# NanoModem.net
KiCad netlist of a schematic drawn in EAGLE
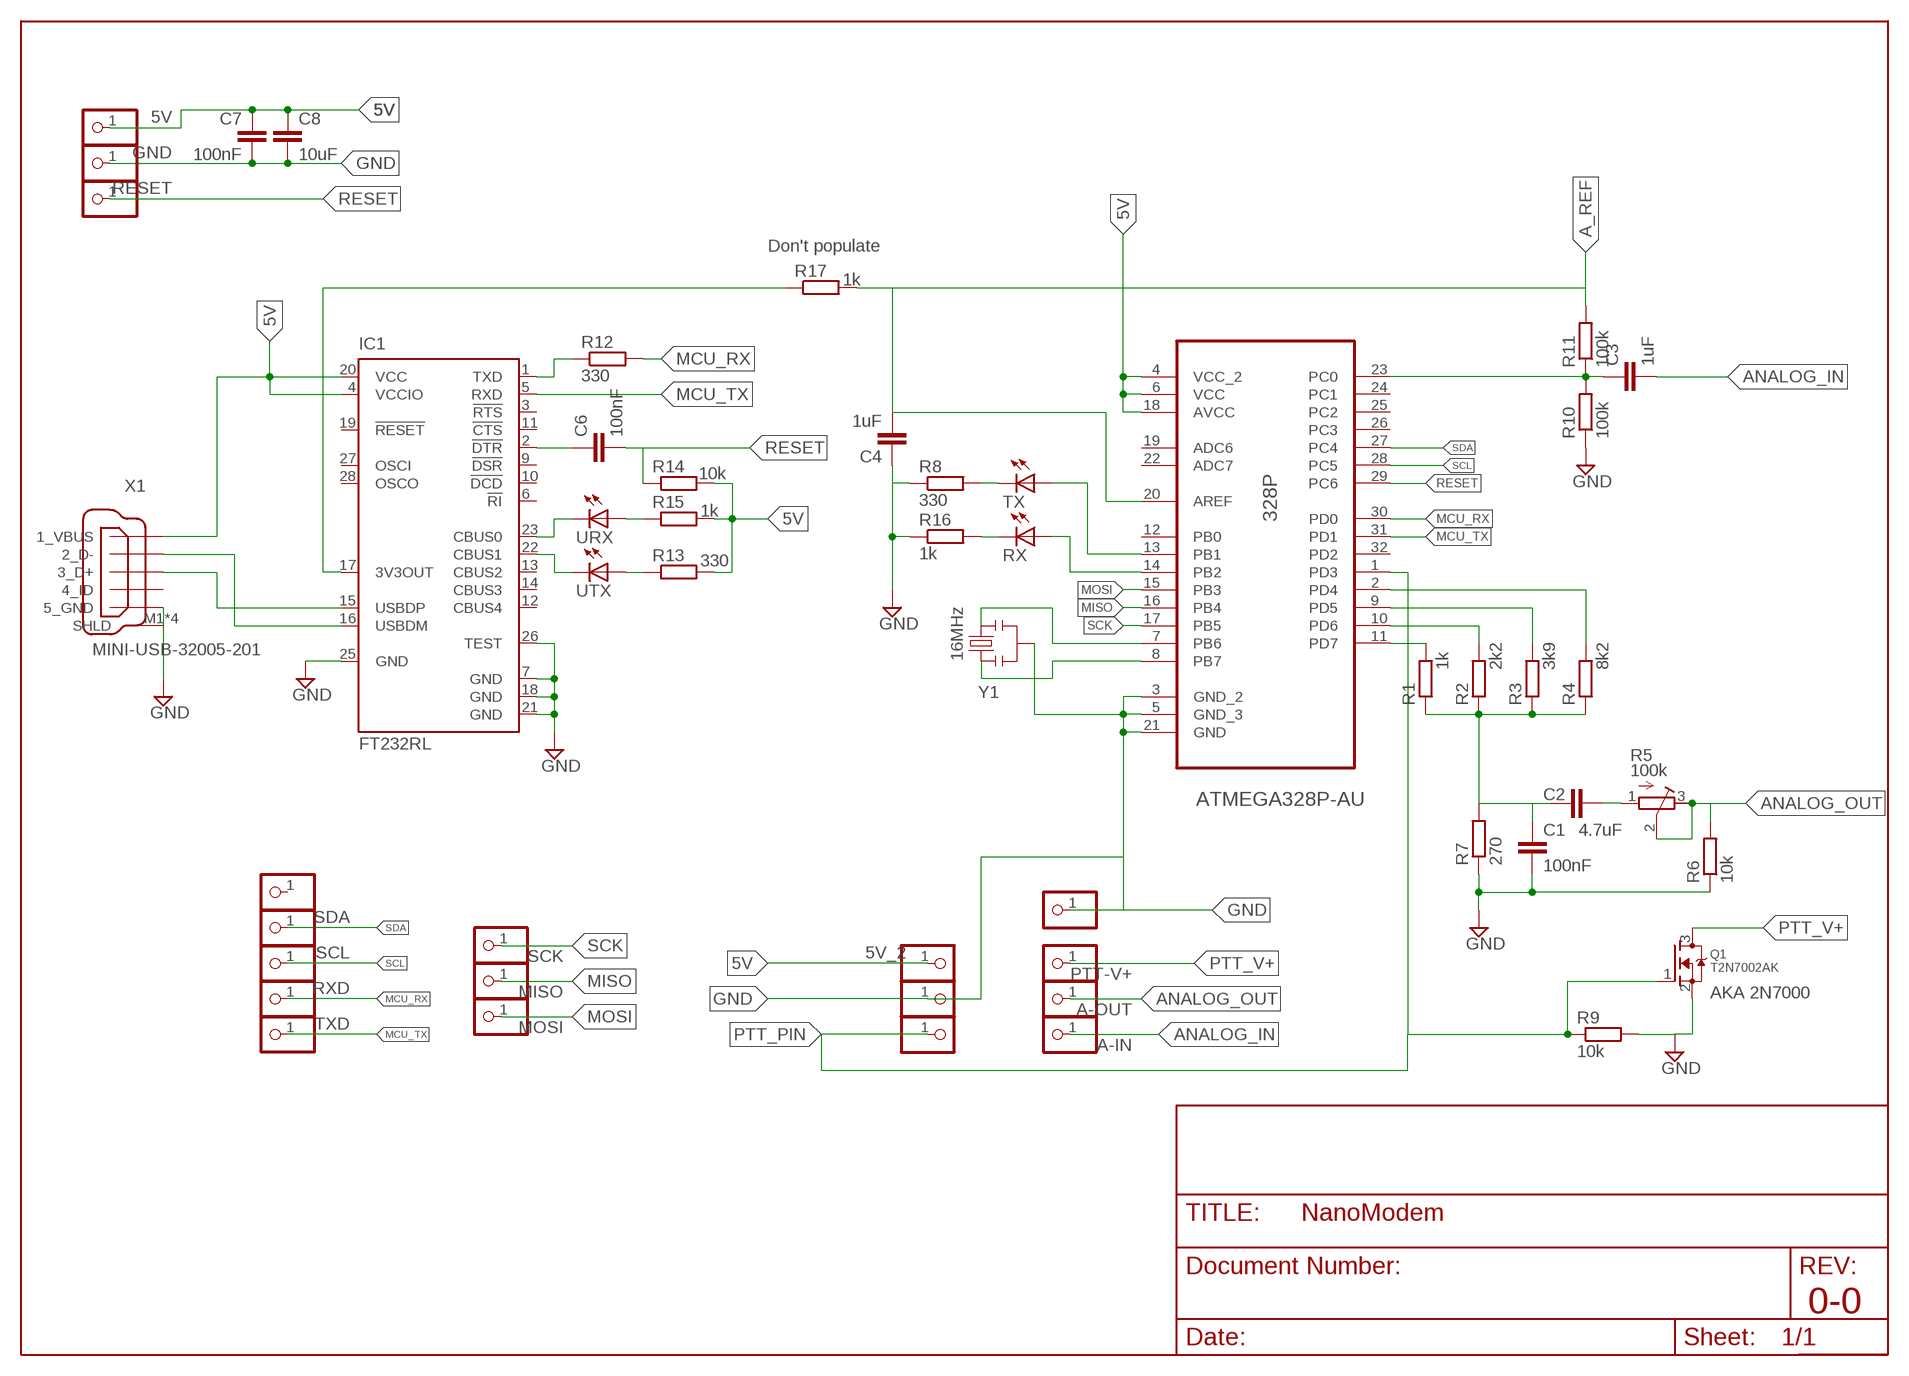
[diagram p0: schematic, sheet 1]

(export (version "E")
  (design (tool "Eeschema 10.0.6"))
  (components
    (comp (ref "3V3")
      (value "PINHD-1X1")
      (footprint "eagle-import:1X01")
      (libsource (lib "eagle-import") (part "PINHD-1X1"))
    )
    (comp (ref "5V")
      (value "PINHD-1X1")
      (footprint "eagle-import:1X01")
      (libsource (lib "eagle-import") (part "PINHD-1X1"))
    )
    (comp (ref "5V_2")
      (value "PINHD-1X1")
      (footprint "eagle-import:1X01")
      (libsource (lib "eagle-import") (part "PINHD-1X1"))
    )
    (comp (ref "328P")
      (value "ATMEGA328P-AU")
      (footprint "eagle-import:QFP80P900X900X120-32N")
      (libsource (lib "eagle-import") (part "ATMEGA328P-AU"))
    )
    (comp (ref "A-IN")
      (value "PINHD-1X1")
      (footprint "eagle-import:1X01")
      (libsource (lib "eagle-import") (part "PINHD-1X1"))
    )
    (comp (ref "A-OUT")
      (value "PINHD-1X1")
      (footprint "eagle-import:1X01")
      (libsource (lib "eagle-import") (part "PINHD-1X1"))
    )
    (comp (ref "C1")
      (value "100nF")
      (footprint "eagle-import:C0603")
      (libsource (lib "eagle-import") (part "C-EUC0603"))
    )
    (comp (ref "C2")
      (value "4.7uF")
      (footprint "eagle-import:C0805")
      (libsource (lib "eagle-import") (part "C-EUC0805"))
    )
    (comp (ref "C3")
      (value "1uF")
      (footprint "eagle-import:C0603")
      (libsource (lib "eagle-import") (part "C-EUC0603"))
    )
    (comp (ref "C4")
      (value "1uF")
      (footprint "eagle-import:C0603")
      (libsource (lib "eagle-import") (part "C-EUC0603"))
    )
    (comp (ref "C6")
      (value "100nF")
      (footprint "eagle-import:C0603")
      (libsource (lib "eagle-import") (part "C-EUC0603"))
    )
    (comp (ref "C7")
      (value "100nF")
      (footprint "eagle-import:C0603")
      (libsource (lib "eagle-import") (part "C-EUC0603"))
    )
    (comp (ref "C8")
      (value "10uF")
      (footprint "eagle-import:C1210")
      (libsource (lib "eagle-import") (part "C-EUC1210"))
    )
    (comp (ref "GND")
      (value "PINHD-1X1")
      (footprint "eagle-import:1X01")
      (libsource (lib "eagle-import") (part "PINHD-1X1"))
    )
    (comp (ref "GND1")
      (value "PINHD-1X1")
      (footprint "eagle-import:1X01")
      (libsource (lib "eagle-import") (part "PINHD-1X1"))
    )
    (comp (ref "GND2")
      (value "PINHD-1X1")
      (footprint "eagle-import:1X01")
      (libsource (lib "eagle-import") (part "PINHD-1X1"))
    )
    (comp (ref "IC1")
      (value "FT232RL")
      (footprint "eagle-import:SSOP28")
      (libsource (lib "eagle-import") (part "FT232RL"))
    )
    (comp (ref "MISO")
      (value "PINHD-1X1")
      (footprint "eagle-import:1X01")
      (libsource (lib "eagle-import") (part "PINHD-1X1"))
    )
    (comp (ref "MOSI")
      (value "PINHD-1X1")
      (footprint "eagle-import:1X01")
      (libsource (lib "eagle-import") (part "PINHD-1X1"))
    )
    (comp (ref "PTT-PIN")
      (value "PINHD-1X1")
      (footprint "eagle-import:1X01")
      (libsource (lib "eagle-import") (part "PINHD-1X1"))
    )
    (comp (ref "PTT-V+")
      (value "PINHD-1X1")
      (footprint "eagle-import:1X01")
      (libsource (lib "eagle-import") (part "PINHD-1X1"))
    )
    (comp (ref "Q1")
      (value "T2N7002AK")
      (footprint "eagle-import:SOT23")
      (libsource (lib "eagle-import") (part "MOSFET-NREFLOW"))
    )
    (comp (ref "R1")
      (value "1k")
      (footprint "eagle-import:R0603")
      (libsource (lib "eagle-import") (part "R-EU_R0603"))
    )
    (comp (ref "R2")
      (value "2k2")
      (footprint "eagle-import:R0603")
      (libsource (lib "eagle-import") (part "R-EU_R0603"))
    )
    (comp (ref "R3")
      (value "3k9")
      (footprint "eagle-import:R0603")
      (libsource (lib "eagle-import") (part "R-EU_R0603"))
    )
    (comp (ref "R4")
      (value "8k2")
      (footprint "eagle-import:R0603")
      (libsource (lib "eagle-import") (part "R-EU_R0603"))
    )
    (comp (ref "R5")
      (value "100k")
      (footprint "eagle-import:RTRIM3339P")
      (libsource (lib "eagle-import") (part "R-TRIMM3339P"))
    )
    (comp (ref "R6")
      (value "10k")
      (footprint "eagle-import:R0603")
      (libsource (lib "eagle-import") (part "R-EU_R0603"))
    )
    (comp (ref "R7")
      (value "270")
      (footprint "eagle-import:R0603")
      (libsource (lib "eagle-import") (part "R-EU_R0603"))
    )
    (comp (ref "R8")
      (value "330")
      (footprint "eagle-import:R0603")
      (libsource (lib "eagle-import") (part "R-EU_R0603"))
    )
    (comp (ref "R9")
      (value "10k")
      (footprint "eagle-import:R0603")
      (libsource (lib "eagle-import") (part "R-EU_R0603"))
    )
    (comp (ref "R10")
      (value "100k")
      (footprint "eagle-import:R0603")
      (libsource (lib "eagle-import") (part "R-EU_R0603"))
    )
    (comp (ref "R11")
      (value "100k")
      (footprint "eagle-import:R0603")
      (libsource (lib "eagle-import") (part "R-EU_R0603"))
    )
    (comp (ref "R12")
      (value "330")
      (footprint "eagle-import:R0603")
      (libsource (lib "eagle-import") (part "R-EU_R0603"))
    )
    (comp (ref "R13")
      (value "330")
      (footprint "eagle-import:R0603")
      (libsource (lib "eagle-import") (part "R-EU_R0603"))
    )
    (comp (ref "R14")
      (value "10k")
      (footprint "eagle-import:R0603")
      (libsource (lib "eagle-import") (part "R-EU_R0603"))
    )
    (comp (ref "R15")
      (value "1k")
      (footprint "eagle-import:R0603")
      (libsource (lib "eagle-import") (part "R-EU_R0603"))
    )
    (comp (ref "R16")
      (value "1k")
      (footprint "eagle-import:R0603")
      (libsource (lib "eagle-import") (part "R-EU_R0603"))
    )
    (comp (ref "R17")
      (value "1k")
      (footprint "eagle-import:R0603")
      (libsource (lib "eagle-import") (part "R-EU_R0603"))
    )
    (comp (ref "RESET")
      (value "PINHD-1X1")
      (footprint "eagle-import:1X01")
      (libsource (lib "eagle-import") (part "PINHD-1X1"))
    )
    (comp (ref "RX")
      (value "LED_ESML0603")
      (footprint "eagle-import:LED_SML0603")
      (libsource (lib "eagle-import") (part "LED_ESML0603"))
    )
    (comp (ref "RXD")
      (value "PINHD-1X1")
      (footprint "eagle-import:1X01")
      (libsource (lib "eagle-import") (part "PINHD-1X1"))
    )
    (comp (ref "SCK")
      (value "PINHD-1X1")
      (footprint "eagle-import:1X01")
      (libsource (lib "eagle-import") (part "PINHD-1X1"))
    )
    (comp (ref "SCL")
      (value "PINHD-1X1")
      (footprint "eagle-import:1X01")
      (libsource (lib "eagle-import") (part "PINHD-1X1"))
    )
    (comp (ref "SDA")
      (value "PINHD-1X1")
      (footprint "eagle-import:1X01")
      (libsource (lib "eagle-import") (part "PINHD-1X1"))
    )
    (comp (ref "TX")
      (value "LED_ESML0603")
      (footprint "eagle-import:LED_SML0603")
      (libsource (lib "eagle-import") (part "LED_ESML0603"))
    )
    (comp (ref "TXD")
      (value "PINHD-1X1")
      (footprint "eagle-import:1X01")
      (libsource (lib "eagle-import") (part "PINHD-1X1"))
    )
    (comp (ref "URX")
      (value "LED_ESML0603")
      (footprint "eagle-import:LED_SML0603")
      (libsource (lib "eagle-import") (part "LED_ESML0603"))
    )
    (comp (ref "UTX")
      (value "LED_ESML0603")
      (footprint "eagle-import:LED_SML0603")
      (libsource (lib "eagle-import") (part "LED_ESML0603"))
    )
    (comp (ref "X1")
      (value "MINI-USB-32005-201")
      (footprint "eagle-import:32005-201")
      (libsource (lib "eagle-import") (part "MINI-USB-32005-201"))
    )
    (comp (ref "Y1")
      (value "16MHz")
      (footprint "eagle-import:RESONATOR-SMD")
      (libsource (lib "eagle-import") (part "RESONATOR16MHZ"))
    )
  )
  (nets
    (net (code "1") (name "5V") (class "Default")
      (node (ref "328P") (pin "18") (pinfunction "AVCC_18") (pintype "power_in"))
      (node (ref "328P") (pin "4") (pinfunction "VCC_2_4") (pintype "power_in"))
      (node (ref "328P") (pin "6") (pinfunction "VCC_6") (pintype "power_in"))
      (node (ref "5V") (pin "1") (pinfunction "1_1") (pintype "passive"))
      (node (ref "5V_2") (pin "1") (pinfunction "1_1") (pintype "passive"))
      (node (ref "C7") (pin "2") (pinfunction "2_2") (pintype "passive"))
      (node (ref "C8") (pin "1") (pinfunction "1_1") (pintype "passive"))
      (node (ref "IC1") (pin "20") (pinfunction "VCC_20") (pintype "power_in"))
      (node (ref "IC1") (pin "4") (pinfunction "VCCIO_4") (pintype "power_in"))
      (node (ref "R13") (pin "2") (pinfunction "2_2") (pintype "passive"))
      (node (ref "R14") (pin "2") (pinfunction "2_2") (pintype "passive"))
      (node (ref "R15") (pin "2") (pinfunction "2_2") (pintype "passive"))
      (node (ref "X1") (pin "1_VBUS") (pinfunction "1_VBUS_1_VBUS") (pintype "passive"))
    )
    (net (code "2") (name "ANALOG_IN") (class "Default")
      (node (ref "A-IN") (pin "1") (pinfunction "1_1") (pintype "passive"))
      (node (ref "C3") (pin "2") (pinfunction "2_2") (pintype "passive"))
    )
    (net (code "3") (name "ANALOG_OUT") (class "Default")
      (node (ref "A-OUT") (pin "1") (pinfunction "1_1") (pintype "passive"))
      (node (ref "R5") (pin "2") (pinfunction "S_2") (pintype "passive"))
      (node (ref "R5") (pin "3") (pinfunction "E_3") (pintype "passive"))
      (node (ref "R6") (pin "2") (pinfunction "2_2") (pintype "passive"))
    )
    (net (code "4") (name "A_REF") (class "Default")
      (node (ref "328P") (pin "20") (pinfunction "AREF_20") (pintype "input"))
      (node (ref "C4") (pin "2") (pinfunction "2_2") (pintype "passive"))
      (node (ref "R11") (pin "2") (pinfunction "2_2") (pintype "passive"))
      (node (ref "R17") (pin "2") (pinfunction "2_2") (pintype "passive"))
    )
    (net (code "5") (name "GND") (class "Default")
      (node (ref "328P") (pin "21") (pinfunction "GND_21") (pintype "passive"))
      (node (ref "328P") (pin "3") (pinfunction "GND_2_3") (pintype "passive"))
      (node (ref "328P") (pin "5") (pinfunction "GND_3_5") (pintype "passive"))
      (node (ref "C1") (pin "2") (pinfunction "2_2") (pintype "passive"))
      (node (ref "C4") (pin "1") (pinfunction "1_1") (pintype "passive"))
      (node (ref "C7") (pin "1") (pinfunction "1_1") (pintype "passive"))
      (node (ref "C8") (pin "2") (pinfunction "2_2") (pintype "passive"))
      (node (ref "GND") (pin "1") (pinfunction "1_1") (pintype "passive"))
      (node (ref "GND1") (pin "1") (pinfunction "1_1") (pintype "passive"))
      (node (ref "GND2") (pin "1") (pinfunction "1_1") (pintype "passive"))
      (node (ref "IC1") (pin "18") (pinfunction "GND_18") (pintype "power_in"))
      (node (ref "IC1") (pin "21") (pinfunction "GND_21") (pintype "power_in"))
      (node (ref "IC1") (pin "25") (pinfunction "GND_25") (pintype "power_in"))
      (node (ref "IC1") (pin "26") (pinfunction "TEST_26") (pintype "input"))
      (node (ref "IC1") (pin "7") (pinfunction "GND_7") (pintype "power_in"))
      (node (ref "Q1") (pin "2") (pinfunction "S_2") (pintype "bidirectional"))
      (node (ref "R10") (pin "1") (pinfunction "1_1") (pintype "passive"))
      (node (ref "R16") (pin "1") (pinfunction "1_1") (pintype "passive"))
      (node (ref "R6") (pin "1") (pinfunction "1_1") (pintype "passive"))
      (node (ref "R7") (pin "1") (pinfunction "1_1") (pintype "passive"))
      (node (ref "R8") (pin "1") (pinfunction "1_1") (pintype "passive"))
      (node (ref "R9") (pin "2") (pinfunction "2_2") (pintype "passive"))
      (node (ref "X1") (pin "5_USB_GND") (pinfunction "5_GND_5_USB_GND") (pintype "passive"))
      (node (ref "X1") (pin "M1") (pinfunction "SHLD_M1") (pintype "passive"))
      (node (ref "X1") (pin "M2") (pinfunction "SHLD_M2") (pintype "passive"))
      (node (ref "X1") (pin "M3") (pinfunction "SHLD_M3") (pintype "passive"))
      (node (ref "X1") (pin "M4") (pinfunction "SHLD_M4") (pintype "passive"))
      (node (ref "Y1") (pin "2") (pinfunction "2_2") (pintype "passive"))
    )
    (net (code "6") (name "MCU_RX") (class "Default")
      (node (ref "328P") (pin "30") (pinfunction "PD0_30") (pintype "bidirectional"))
      (node (ref "R12") (pin "2") (pinfunction "2_2") (pintype "passive"))
      (node (ref "RXD") (pin "1") (pinfunction "1_1") (pintype "passive"))
    )
    (net (code "7") (name "MCU_TX") (class "Default")
      (node (ref "328P") (pin "31") (pinfunction "PD1_31") (pintype "bidirectional"))
      (node (ref "IC1") (pin "5") (pinfunction "RXD_5") (pintype "input"))
      (node (ref "TXD") (pin "1") (pinfunction "1_1") (pintype "passive"))
    )
    (net (code "8") (name "MISO") (class "Default")
      (node (ref "328P") (pin "16") (pinfunction "PB4_16") (pintype "bidirectional"))
      (node (ref "MISO") (pin "1") (pinfunction "1_1") (pintype "passive"))
    )
    (net (code "9") (name "MOSI") (class "Default")
      (node (ref "328P") (pin "15") (pinfunction "PB3_15") (pintype "bidirectional"))
      (node (ref "MOSI") (pin "1") (pinfunction "1_1") (pintype "passive"))
    )
    (net (code "10") (name "Net-(328P-PB1)") (class "Default")
      (node (ref "328P") (pin "13") (pinfunction "PB1_13") (pintype "bidirectional"))
      (node (ref "TX") (pin "A") (pinfunction "A_A") (pintype "passive"))
    )
    (net (code "11") (name "Net-(328P-PB2)") (class "Default")
      (node (ref "328P") (pin "14") (pinfunction "PB2_14") (pintype "bidirectional"))
      (node (ref "RX") (pin "A") (pinfunction "A_A") (pintype "passive"))
    )
    (net (code "12") (name "Net-(328P-PB6)") (class "Default")
      (node (ref "328P") (pin "7") (pinfunction "PB6_7") (pintype "bidirectional"))
      (node (ref "Y1") (pin "3") (pinfunction "3_3") (pintype "passive"))
    )
    (net (code "13") (name "Net-(328P-PB7)") (class "Default")
      (node (ref "328P") (pin "8") (pinfunction "PB7_8") (pintype "bidirectional"))
      (node (ref "Y1") (pin "1") (pinfunction "1_1") (pintype "passive"))
    )
    (net (code "14") (name "Net-(328P-PC0)") (class "Default")
      (node (ref "328P") (pin "23") (pinfunction "PC0_23") (pintype "bidirectional"))
      (node (ref "C3") (pin "1") (pinfunction "1_1") (pintype "passive"))
      (node (ref "R10") (pin "2") (pinfunction "2_2") (pintype "passive"))
      (node (ref "R11") (pin "1") (pinfunction "1_1") (pintype "passive"))
    )
    (net (code "15") (name "Net-(328P-PD4)") (class "Default")
      (node (ref "328P") (pin "2") (pinfunction "PD4_2") (pintype "bidirectional"))
      (node (ref "R4") (pin "2") (pinfunction "2_2") (pintype "passive"))
    )
    (net (code "16") (name "Net-(328P-PD5)") (class "Default")
      (node (ref "328P") (pin "9") (pinfunction "PD5_9") (pintype "bidirectional"))
      (node (ref "R3") (pin "2") (pinfunction "2_2") (pintype "passive"))
    )
    (net (code "17") (name "Net-(328P-PD6)") (class "Default")
      (node (ref "328P") (pin "10") (pinfunction "PD6_10") (pintype "bidirectional"))
      (node (ref "R2") (pin "2") (pinfunction "2_2") (pintype "passive"))
    )
    (net (code "18") (name "Net-(328P-PD7)") (class "Default")
      (node (ref "328P") (pin "11") (pinfunction "PD7_11") (pintype "bidirectional"))
      (node (ref "R1") (pin "2") (pinfunction "2_2") (pintype "passive"))
    )
    (net (code "19") (name "Net-(C1-Pad1)") (class "Default")
      (node (ref "C1") (pin "1") (pinfunction "1_1") (pintype "passive"))
      (node (ref "C2") (pin "2") (pinfunction "2_2") (pintype "passive"))
      (node (ref "R1") (pin "1") (pinfunction "1_1") (pintype "passive"))
      (node (ref "R2") (pin "1") (pinfunction "1_1") (pintype "passive"))
      (node (ref "R3") (pin "1") (pinfunction "1_1") (pintype "passive"))
      (node (ref "R4") (pin "1") (pinfunction "1_1") (pintype "passive"))
      (node (ref "R7") (pin "2") (pinfunction "2_2") (pintype "passive"))
    )
    (net (code "20") (name "Net-(IC1-3V3OUT)") (class "Default")
      (node (ref "IC1") (pin "17") (pinfunction "3V3OUT_17") (pintype "output"))
      (node (ref "R17") (pin "1") (pinfunction "1_1") (pintype "passive"))
    )
    (net (code "21") (name "Net-(IC1-CBUS0)") (class "Default")
      (node (ref "IC1") (pin "23") (pinfunction "CBUS0_23") (pintype "bidirectional"))
      (node (ref "URX") (pin "C") (pinfunction "C_C") (pintype "passive"))
    )
    (net (code "22") (name "Net-(IC1-CBUS1)") (class "Default")
      (node (ref "IC1") (pin "22") (pinfunction "CBUS1_22") (pintype "bidirectional"))
      (node (ref "UTX") (pin "C") (pinfunction "C_C") (pintype "passive"))
    )
    (net (code "23") (name "Net-(IC1-TXD)") (class "Default")
      (node (ref "IC1") (pin "1") (pinfunction "TXD_1") (pintype "output"))
      (node (ref "R12") (pin "1") (pinfunction "1_1") (pintype "passive"))
    )
    (net (code "24") (name "Net-(IC1-USBDM)") (class "Default")
      (node (ref "IC1") (pin "16") (pinfunction "USBDM_16") (pintype "bidirectional"))
      (node (ref "X1") (pin "2_D-") (pinfunction "2_D-_2_D-") (pintype "passive"))
    )
    (net (code "25") (name "Net-(IC1-USBDP)") (class "Default")
      (node (ref "IC1") (pin "15") (pinfunction "USBDP_15") (pintype "bidirectional"))
      (node (ref "X1") (pin "3_D+") (pinfunction "3_D+_3_D+") (pintype "passive"))
    )
    (net (code "26") (name "Net-(IC1-~{DTR})") (class "Default")
      (node (ref "C6") (pin "1") (pinfunction "1_1") (pintype "passive"))
      (node (ref "IC1") (pin "2") (pinfunction "~{DTR}_2") (pintype "output"))
    )
    (net (code "27") (name "Net-(R5-A)") (class "Default")
      (node (ref "C2") (pin "1") (pinfunction "1_1") (pintype "passive"))
      (node (ref "R5") (pin "1") (pinfunction "A_1") (pintype "passive"))
    )
    (net (code "28") (name "Net-(R8-Pad2)") (class "Default")
      (node (ref "R8") (pin "2") (pinfunction "2_2") (pintype "passive"))
      (node (ref "TX") (pin "C") (pinfunction "C_C") (pintype "passive"))
    )
    (net (code "29") (name "Net-(R13-Pad1)") (class "Default")
      (node (ref "R13") (pin "1") (pinfunction "1_1") (pintype "passive"))
      (node (ref "UTX") (pin "A") (pinfunction "A_A") (pintype "passive"))
    )
    (net (code "30") (name "Net-(R15-Pad1)") (class "Default")
      (node (ref "R15") (pin "1") (pinfunction "1_1") (pintype "passive"))
      (node (ref "URX") (pin "A") (pinfunction "A_A") (pintype "passive"))
    )
    (net (code "31") (name "Net-(R16-Pad2)") (class "Default")
      (node (ref "R16") (pin "2") (pinfunction "2_2") (pintype "passive"))
      (node (ref "RX") (pin "C") (pinfunction "C_C") (pintype "passive"))
    )
    (net (code "32") (name "PTT_PIN") (class "Default")
      (node (ref "328P") (pin "1") (pinfunction "PD3_1") (pintype "bidirectional"))
      (node (ref "PTT-PIN") (pin "1") (pinfunction "1_1") (pintype "passive"))
      (node (ref "Q1") (pin "1") (pinfunction "G_1") (pintype "bidirectional"))
      (node (ref "R9") (pin "1") (pinfunction "1_1") (pintype "passive"))
    )
    (net (code "33") (name "PTT_V+") (class "Default")
      (node (ref "PTT-V+") (pin "1") (pinfunction "1_1") (pintype "passive"))
      (node (ref "Q1") (pin "3") (pinfunction "D_3") (pintype "bidirectional"))
    )
    (net (code "34") (name "RESET") (class "Default")
      (node (ref "328P") (pin "29") (pinfunction "PC6_29") (pintype "bidirectional"))
      (node (ref "C6") (pin "2") (pinfunction "2_2") (pintype "passive"))
      (node (ref "R14") (pin "1") (pinfunction "1_1") (pintype "passive"))
      (node (ref "RESET") (pin "1") (pinfunction "1_1") (pintype "passive"))
    )
    (net (code "35") (name "SCK") (class "Default")
      (node (ref "328P") (pin "17") (pinfunction "PB5_17") (pintype "bidirectional"))
      (node (ref "SCK") (pin "1") (pinfunction "1_1") (pintype "passive"))
    )
    (net (code "36") (name "SCL") (class "Default")
      (node (ref "328P") (pin "28") (pinfunction "PC5_28") (pintype "bidirectional"))
      (node (ref "SCL") (pin "1") (pinfunction "1_1") (pintype "passive"))
    )
    (net (code "37") (name "SDA") (class "Default")
      (node (ref "328P") (pin "27") (pinfunction "PC4_27") (pintype "bidirectional"))
      (node (ref "SDA") (pin "1") (pinfunction "1_1") (pintype "passive"))
    )
    (net (code "38") (name "unconnected-(3V3-Pad1)") (class "Default")
      (node (ref "3V3") (pin "1") (pinfunction "1_1") (pintype "passive"))
    )
    (net (code "39") (name "unconnected-(328P-ADC6-Pad19)") (class "Default")
      (node (ref "328P") (pin "19") (pinfunction "ADC6_19") (pintype "input"))
    )
    (net (code "40") (name "unconnected-(328P-ADC7-Pad22)") (class "Default")
      (node (ref "328P") (pin "22") (pinfunction "ADC7_22") (pintype "input"))
    )
    (net (code "41") (name "unconnected-(328P-PB0-Pad12)") (class "Default")
      (node (ref "328P") (pin "12") (pinfunction "PB0_12") (pintype "bidirectional"))
    )
    (net (code "42") (name "unconnected-(328P-PC1-Pad24)") (class "Default")
      (node (ref "328P") (pin "24") (pinfunction "PC1_24") (pintype "bidirectional"))
    )
    (net (code "43") (name "unconnected-(328P-PC2-Pad25)") (class "Default")
      (node (ref "328P") (pin "25") (pinfunction "PC2_25") (pintype "bidirectional"))
    )
    (net (code "44") (name "unconnected-(328P-PC3-Pad26)") (class "Default")
      (node (ref "328P") (pin "26") (pinfunction "PC3_26") (pintype "bidirectional"))
    )
    (net (code "45") (name "unconnected-(328P-PD2-Pad32)") (class "Default")
      (node (ref "328P") (pin "32") (pinfunction "PD2_32") (pintype "bidirectional"))
    )
    (net (code "46") (name "unconnected-(IC1-CBUS2-Pad13)") (class "Default")
      (node (ref "IC1") (pin "13") (pinfunction "CBUS2_13") (pintype "bidirectional"))
    )
    (net (code "47") (name "unconnected-(IC1-CBUS3-Pad14)") (class "Default")
      (node (ref "IC1") (pin "14") (pinfunction "CBUS3_14") (pintype "bidirectional"))
    )
    (net (code "48") (name "unconnected-(IC1-CBUS4-Pad12)") (class "Default")
      (node (ref "IC1") (pin "12") (pinfunction "CBUS4_12") (pintype "bidirectional"))
    )
    (net (code "49") (name "unconnected-(IC1-OSCI-Pad27)") (class "Default")
      (node (ref "IC1") (pin "27") (pinfunction "OSCI_27") (pintype "input"))
    )
    (net (code "50") (name "unconnected-(IC1-OSCO-Pad28)") (class "Default")
      (node (ref "IC1") (pin "28") (pinfunction "OSCO_28") (pintype "output"))
    )
    (net (code "51") (name "unconnected-(IC1-~{CTS}-Pad11)") (class "Default")
      (node (ref "IC1") (pin "11") (pinfunction "~{CTS}_11") (pintype "input"))
    )
    (net (code "52") (name "unconnected-(IC1-~{DCD}-Pad10)") (class "Default")
      (node (ref "IC1") (pin "10") (pinfunction "~{DCD}_10") (pintype "input"))
    )
    (net (code "53") (name "unconnected-(IC1-~{DSR}-Pad9)") (class "Default")
      (node (ref "IC1") (pin "9") (pinfunction "~{DSR}_9") (pintype "input"))
    )
    (net (code "54") (name "unconnected-(IC1-~{RESET}-Pad19)") (class "Default")
      (node (ref "IC1") (pin "19") (pinfunction "~{RESET}_19") (pintype "input"))
    )
    (net (code "55") (name "unconnected-(IC1-~{RI}-Pad6)") (class "Default")
      (node (ref "IC1") (pin "6") (pinfunction "~{RI}_6") (pintype "input"))
    )
    (net (code "56") (name "unconnected-(IC1-~{RTS}-Pad3)") (class "Default")
      (node (ref "IC1") (pin "3") (pinfunction "~{RTS}_3") (pintype "output"))
    )
    (net (code "57") (name "unconnected-(X1-Pad4_ID)") (class "Default")
      (node (ref "X1") (pin "4_ID") (pinfunction "4_ID_4_ID") (pintype "passive"))
    )
  )
)
